# Main.net
KiCad netlist of a schematic drawn in Altium Designer
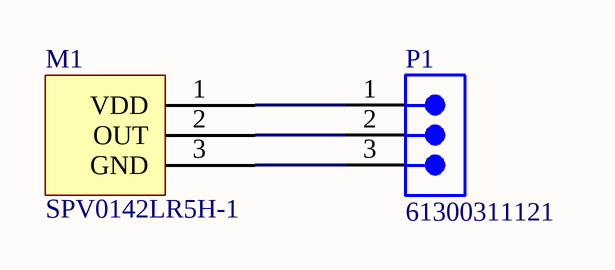
[diagram p0: Main.SchDoc]

(export (version "E")
  (design (tool "Eeschema 10.0.6"))
  (components
    (comp (ref "M1")
      (value "SPV0142LR5H-1")
      (footprint "SPV0142LR5H-1")
      (libsource (lib "SPV0142LR5H-1") (part "SPV0142LR5H-1"))
    )
    (comp (ref "P1")
      (value "61300311121")
      (footprint "61300311121")
      (description "THT Vertical Pin Header WR-PHD, Pitch 2.54 mm, Single Row, 3 pins")
      (libsource (lib "Altium Content Vault") (part "Header_Male_1R_03P"))
    )
  )
  (nets
    (net (code "1") (name "Net-(M1-GND)") (class "Default")
      (node (ref "M1") (pin "3") (pinfunction "GND_3") (pintype "passive"))
      (node (ref "P1") (pin "3") (pinfunction "3_3") (pintype "passive"))
    )
    (net (code "2") (name "Net-(M1-OUT)") (class "Default")
      (node (ref "M1") (pin "2") (pinfunction "OUT_2") (pintype "passive"))
      (node (ref "P1") (pin "2") (pinfunction "2_2") (pintype "passive"))
    )
    (net (code "3") (name "Net-(M1-VDD)") (class "Default")
      (node (ref "M1") (pin "1") (pinfunction "VDD_1") (pintype "passive"))
      (node (ref "P1") (pin "1") (pinfunction "1_1") (pintype "passive"))
    )
  )
)
